# ZB3.net
KiCad netlist of a schematic drawn in Altium Designer
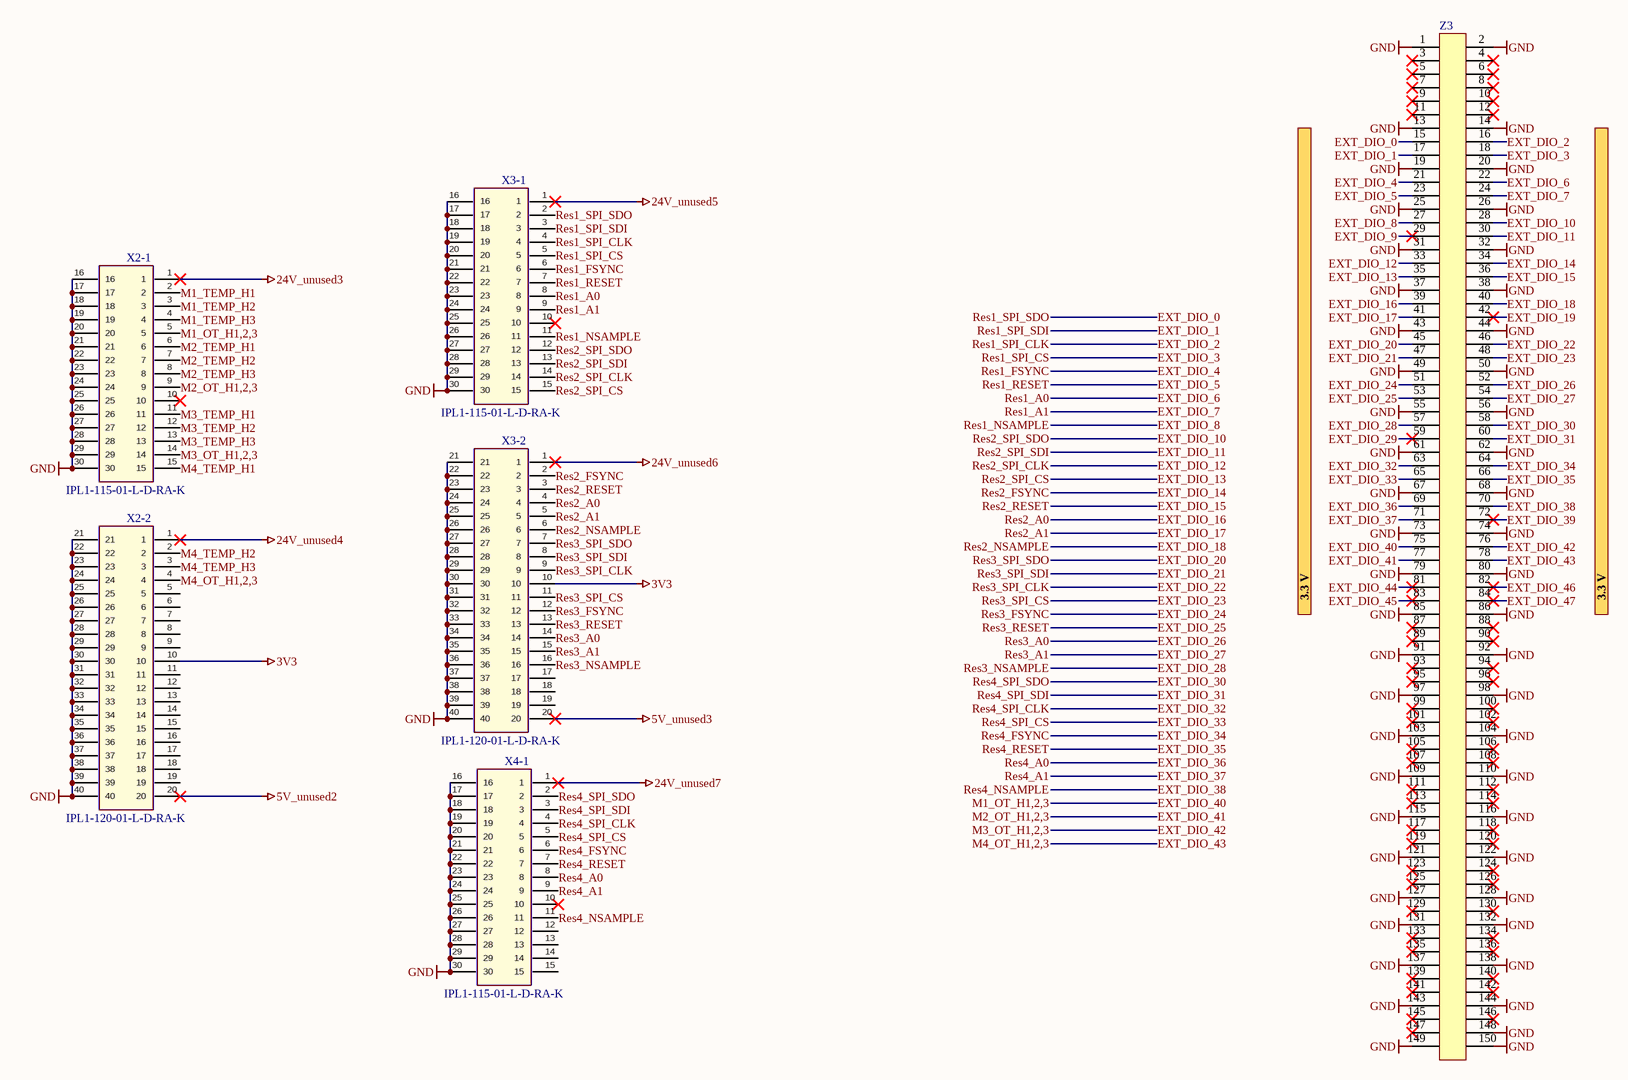
[diagram p0: ZB3.SchDoc]

(export (version "E")
  (design (tool "Eeschema 10.0.6"))
  (components
    (comp (ref "X2-1")
      (value "IPL1-115-01-L-D-RA-K")
      (footprint "IPL1-115-01-XX-D-RA")
      (description "Terminal Assembly, Double Row, Right Angle, Thru-Hole, 2.54 mm x 2.54 mm Pitch, 30 Pins")
      (fields (field (name "MANUFACTURER") "SAMTEC") (field (name "CREATED FROM") "TWendt"))
      (libsource (lib "user") (part "IPL1-115-01-XX-D-RA"))
    )
    (comp (ref "X2-2")
      (value "IPL1-120-01-L-D-RA-K")
      (footprint "IPL1-120-01-XX-D-RA")
      (description "Terminal Assembly, Double Row, Right Angle, Thru-Hole, 2.54 mm x 2.54 mm Pitch, 40 Pins")
      (fields (field (name "MANUFACTURER") "SAMTEC") (field (name "CREATED FROM") "TWendt"))
      (libsource (lib "user") (part "IPL1-120-01-XX-D-RA"))
    )
    (comp (ref "X3-1")
      (value "IPL1-115-01-L-D-RA-K")
      (footprint "IPL1-115-01-XX-D-RA")
      (description "Terminal Assembly, Double Row, Right Angle, Thru-Hole, 2.54 mm x 2.54 mm Pitch, 30 Pins")
      (fields (field (name "MANUFACTURER") "SAMTEC") (field (name "CREATED FROM") "TWendt"))
      (libsource (lib "user") (part "IPL1-115-01-XX-D-RA"))
    )
    (comp (ref "X3-2")
      (value "IPL1-120-01-L-D-RA-K")
      (footprint "IPL1-120-01-XX-D-RA")
      (description "Terminal Assembly, Double Row, Right Angle, Thru-Hole, 2.54 mm x 2.54 mm Pitch, 40 Pins")
      (fields (field (name "MANUFACTURER") "SAMTEC") (field (name "CREATED FROM") "TWendt"))
      (libsource (lib "user") (part "IPL1-120-01-XX-D-RA"))
    )
    (comp (ref "X4-1")
      (value "IPL1-115-01-L-D-RA-K")
      (footprint "IPL1-115-01-XX-D-RA")
      (description "Terminal Assembly, Double Row, Right Angle, Thru-Hole, 2.54 mm x 2.54 mm Pitch, 30 Pins")
      (fields (field (name "MANUFACTURER") "SAMTEC") (field (name "CREATED FROM") "TWendt"))
      (libsource (lib "user") (part "IPL1-115-01-XX-D-RA"))
    )
    (comp (ref "Z3")
      (value "~")
      (footprint "ERM8-075-02.0-L-DV")
      (description "0.80 mm Edge Rate Rugged High Speed")
      (fields
        (field (name "MANUFACTURER PART NUMBER") "ERM8-075-02.0-L-DV-TR")
        (field (name "MANUFACTURER") "SAMTEC")
        (field (name "CREATED FROM") "AGeiger")
      )
      (libsource (lib "user") (part "CON-150"))
    )
  )
  (nets
    (net (code "1") (name "/EXT_DIO_0") (class "Default")
      (node (ref "X3-1") (pin "2") (pinfunction "2_2") (pintype "passive"))
      (node (ref "Z3") (pin "15") (pinfunction "15_15") (pintype "passive"))
    )
    (net (code "2") (name "/EXT_DIO_1") (class "Default")
      (node (ref "X3-1") (pin "3") (pinfunction "3_3") (pintype "passive"))
      (node (ref "Z3") (pin "17") (pinfunction "17_17") (pintype "passive"))
    )
    (net (code "3") (name "/EXT_DIO_2") (class "Default")
      (node (ref "X3-1") (pin "4") (pinfunction "4_4") (pintype "passive"))
      (node (ref "Z3") (pin "16") (pinfunction "16_16") (pintype "passive"))
    )
    (net (code "4") (name "/EXT_DIO_3") (class "Default")
      (node (ref "X3-1") (pin "5") (pinfunction "5_5") (pintype "passive"))
      (node (ref "Z3") (pin "18") (pinfunction "18_18") (pintype "passive"))
    )
    (net (code "5") (name "/EXT_DIO_4") (class "Default")
      (node (ref "X3-1") (pin "6") (pinfunction "6_6") (pintype "passive"))
      (node (ref "Z3") (pin "21") (pinfunction "21_21") (pintype "passive"))
    )
    (net (code "6") (name "/EXT_DIO_5") (class "Default")
      (node (ref "X3-1") (pin "7") (pinfunction "7_7") (pintype "passive"))
      (node (ref "Z3") (pin "23") (pinfunction "23_23") (pintype "passive"))
    )
    (net (code "7") (name "/EXT_DIO_6") (class "Default")
      (node (ref "X3-1") (pin "8") (pinfunction "8_8") (pintype "passive"))
      (node (ref "Z3") (pin "22") (pinfunction "22_22") (pintype "passive"))
    )
    (net (code "8") (name "/EXT_DIO_7") (class "Default")
      (node (ref "X3-1") (pin "9") (pinfunction "9_9") (pintype "passive"))
      (node (ref "Z3") (pin "24") (pinfunction "24_24") (pintype "passive"))
    )
    (net (code "9") (name "/EXT_DIO_8") (class "Default")
      (node (ref "X3-1") (pin "11") (pinfunction "11_11") (pintype "passive"))
      (node (ref "Z3") (pin "27") (pinfunction "27_27") (pintype "passive"))
    )
    (net (code "10") (name "/EXT_DIO_9") (class "Default")
      (node (ref "Z3") (pin "29") (pinfunction "29_29") (pintype "passive+no_connect"))
    )
    (net (code "11") (name "/EXT_DIO_10") (class "Default")
      (node (ref "X3-1") (pin "12") (pinfunction "12_12") (pintype "passive"))
      (node (ref "Z3") (pin "28") (pinfunction "28_28") (pintype "passive"))
    )
    (net (code "12") (name "/EXT_DIO_11") (class "Default")
      (node (ref "X3-1") (pin "13") (pinfunction "13_13") (pintype "passive"))
      (node (ref "Z3") (pin "30") (pinfunction "30_30") (pintype "passive"))
    )
    (net (code "13") (name "/EXT_DIO_12") (class "Default")
      (node (ref "X3-1") (pin "14") (pinfunction "14_14") (pintype "passive"))
      (node (ref "Z3") (pin "33") (pinfunction "33_33") (pintype "passive"))
    )
    (net (code "14") (name "/EXT_DIO_13") (class "Default")
      (node (ref "X3-1") (pin "15") (pinfunction "15_15") (pintype "passive"))
      (node (ref "Z3") (pin "35") (pinfunction "35_35") (pintype "passive"))
    )
    (net (code "15") (name "/EXT_DIO_14") (class "Default")
      (node (ref "X3-2") (pin "2") (pinfunction "2_2") (pintype "passive"))
      (node (ref "Z3") (pin "34") (pinfunction "34_34") (pintype "passive"))
    )
    (net (code "16") (name "/EXT_DIO_15") (class "Default")
      (node (ref "X3-2") (pin "3") (pinfunction "3_3") (pintype "passive"))
      (node (ref "Z3") (pin "36") (pinfunction "36_36") (pintype "passive"))
    )
    (net (code "17") (name "/EXT_DIO_16") (class "Default")
      (node (ref "X3-2") (pin "4") (pinfunction "4_4") (pintype "passive"))
      (node (ref "Z3") (pin "39") (pinfunction "39_39") (pintype "passive"))
    )
    (net (code "18") (name "/EXT_DIO_17") (class "Default")
      (node (ref "X3-2") (pin "5") (pinfunction "5_5") (pintype "passive"))
      (node (ref "Z3") (pin "41") (pinfunction "41_41") (pintype "passive"))
    )
    (net (code "19") (name "/EXT_DIO_18") (class "Default")
      (node (ref "X3-2") (pin "6") (pinfunction "6_6") (pintype "passive"))
      (node (ref "Z3") (pin "40") (pinfunction "40_40") (pintype "passive"))
    )
    (net (code "20") (name "/EXT_DIO_19") (class "Default")
      (node (ref "Z3") (pin "42") (pinfunction "42_42") (pintype "passive+no_connect"))
    )
    (net (code "21") (name "/EXT_DIO_20") (class "Default")
      (node (ref "X3-2") (pin "7") (pinfunction "7_7") (pintype "passive"))
      (node (ref "Z3") (pin "45") (pinfunction "45_45") (pintype "passive"))
    )
    (net (code "22") (name "/EXT_DIO_21") (class "Default")
      (node (ref "X3-2") (pin "8") (pinfunction "8_8") (pintype "passive"))
      (node (ref "Z3") (pin "47") (pinfunction "47_47") (pintype "passive"))
    )
    (net (code "23") (name "/EXT_DIO_22") (class "Default")
      (node (ref "X3-2") (pin "9") (pinfunction "9_9") (pintype "passive"))
      (node (ref "Z3") (pin "46") (pinfunction "46_46") (pintype "passive"))
    )
    (net (code "24") (name "/EXT_DIO_23") (class "Default")
      (node (ref "X3-2") (pin "11") (pinfunction "11_11") (pintype "passive"))
      (node (ref "Z3") (pin "48") (pinfunction "48_48") (pintype "passive"))
    )
    (net (code "25") (name "/EXT_DIO_24") (class "Default")
      (node (ref "X3-2") (pin "12") (pinfunction "12_12") (pintype "passive"))
      (node (ref "Z3") (pin "51") (pinfunction "51_51") (pintype "passive"))
    )
    (net (code "26") (name "/EXT_DIO_25") (class "Default")
      (node (ref "X3-2") (pin "13") (pinfunction "13_13") (pintype "passive"))
      (node (ref "Z3") (pin "53") (pinfunction "53_53") (pintype "passive"))
    )
    (net (code "27") (name "/EXT_DIO_26") (class "Default")
      (node (ref "X3-2") (pin "14") (pinfunction "14_14") (pintype "passive"))
      (node (ref "Z3") (pin "52") (pinfunction "52_52") (pintype "passive"))
    )
    (net (code "28") (name "/EXT_DIO_27") (class "Default")
      (node (ref "X3-2") (pin "15") (pinfunction "15_15") (pintype "passive"))
      (node (ref "Z3") (pin "54") (pinfunction "54_54") (pintype "passive"))
    )
    (net (code "29") (name "/EXT_DIO_28") (class "Default")
      (node (ref "X3-2") (pin "16") (pinfunction "16_16") (pintype "passive"))
      (node (ref "Z3") (pin "57") (pinfunction "57_57") (pintype "passive"))
    )
    (net (code "30") (name "/EXT_DIO_29") (class "Default")
      (node (ref "Z3") (pin "59") (pinfunction "59_59") (pintype "passive+no_connect"))
    )
    (net (code "31") (name "/EXT_DIO_30") (class "Default")
      (node (ref "X4-1") (pin "2") (pinfunction "2_2") (pintype "passive"))
      (node (ref "Z3") (pin "58") (pinfunction "58_58") (pintype "passive"))
    )
    (net (code "32") (name "/EXT_DIO_31") (class "Default")
      (node (ref "X4-1") (pin "3") (pinfunction "3_3") (pintype "passive"))
      (node (ref "Z3") (pin "60") (pinfunction "60_60") (pintype "passive"))
    )
    (net (code "33") (name "/EXT_DIO_32") (class "Default")
      (node (ref "X4-1") (pin "4") (pinfunction "4_4") (pintype "passive"))
      (node (ref "Z3") (pin "63") (pinfunction "63_63") (pintype "passive"))
    )
    (net (code "34") (name "/EXT_DIO_33") (class "Default")
      (node (ref "X4-1") (pin "5") (pinfunction "5_5") (pintype "passive"))
      (node (ref "Z3") (pin "65") (pinfunction "65_65") (pintype "passive"))
    )
    (net (code "35") (name "/EXT_DIO_34") (class "Default")
      (node (ref "X4-1") (pin "6") (pinfunction "6_6") (pintype "passive"))
      (node (ref "Z3") (pin "64") (pinfunction "64_64") (pintype "passive"))
    )
    (net (code "36") (name "/EXT_DIO_35") (class "Default")
      (node (ref "X4-1") (pin "7") (pinfunction "7_7") (pintype "passive"))
      (node (ref "Z3") (pin "66") (pinfunction "66_66") (pintype "passive"))
    )
    (net (code "37") (name "/EXT_DIO_36") (class "Default")
      (node (ref "X4-1") (pin "8") (pinfunction "8_8") (pintype "passive"))
      (node (ref "Z3") (pin "69") (pinfunction "69_69") (pintype "passive"))
    )
    (net (code "38") (name "/EXT_DIO_37") (class "Default")
      (node (ref "X4-1") (pin "9") (pinfunction "9_9") (pintype "passive"))
      (node (ref "Z3") (pin "71") (pinfunction "71_71") (pintype "passive"))
    )
    (net (code "39") (name "/EXT_DIO_38") (class "Default")
      (node (ref "X4-1") (pin "11") (pinfunction "11_11") (pintype "passive"))
      (node (ref "Z3") (pin "70") (pinfunction "70_70") (pintype "passive"))
    )
    (net (code "40") (name "/EXT_DIO_39") (class "Default")
      (node (ref "Z3") (pin "72") (pinfunction "72_72") (pintype "passive+no_connect"))
    )
    (net (code "41") (name "/EXT_DIO_40") (class "Default")
      (node (ref "X2-1") (pin "5") (pinfunction "5_5") (pintype "passive"))
      (node (ref "Z3") (pin "75") (pinfunction "75_75") (pintype "passive"))
    )
    (net (code "42") (name "/EXT_DIO_41") (class "Default")
      (node (ref "X2-1") (pin "9") (pinfunction "9_9") (pintype "passive"))
      (node (ref "Z3") (pin "77") (pinfunction "77_77") (pintype "passive"))
    )
    (net (code "43") (name "/EXT_DIO_42") (class "Default")
      (node (ref "X2-1") (pin "14") (pinfunction "14_14") (pintype "passive"))
      (node (ref "Z3") (pin "76") (pinfunction "76_76") (pintype "passive"))
    )
    (net (code "44") (name "/EXT_DIO_43") (class "Default")
      (node (ref "X2-2") (pin "4") (pinfunction "4_4") (pintype "passive"))
      (node (ref "Z3") (pin "78") (pinfunction "78_78") (pintype "passive"))
    )
    (net (code "45") (name "/EXT_DIO_44") (class "Default")
      (node (ref "Z3") (pin "81") (pinfunction "81_81") (pintype "passive+no_connect"))
    )
    (net (code "46") (name "/EXT_DIO_45") (class "Default")
      (node (ref "Z3") (pin "83") (pinfunction "83_83") (pintype "passive+no_connect"))
    )
    (net (code "47") (name "/EXT_DIO_46") (class "Default")
      (node (ref "Z3") (pin "82") (pinfunction "82_82") (pintype "passive+no_connect"))
    )
    (net (code "48") (name "/EXT_DIO_47") (class "Default")
      (node (ref "Z3") (pin "84") (pinfunction "84_84") (pintype "passive+no_connect"))
    )
    (net (code "49") (name "/M1_TEMP_H1") (class "Default")
      (node (ref "X2-1") (pin "2") (pinfunction "2_2") (pintype "passive"))
    )
    (net (code "50") (name "/M1_TEMP_H2") (class "Default")
      (node (ref "X2-1") (pin "3") (pinfunction "3_3") (pintype "passive"))
    )
    (net (code "51") (name "/M1_TEMP_H3") (class "Default")
      (node (ref "X2-1") (pin "4") (pinfunction "4_4") (pintype "passive"))
    )
    (net (code "52") (name "/M2_TEMP_H1") (class "Default")
      (node (ref "X2-1") (pin "6") (pinfunction "6_6") (pintype "passive"))
    )
    (net (code "53") (name "/M2_TEMP_H2") (class "Default")
      (node (ref "X2-1") (pin "7") (pinfunction "7_7") (pintype "passive"))
    )
    (net (code "54") (name "/M2_TEMP_H3") (class "Default")
      (node (ref "X2-1") (pin "8") (pinfunction "8_8") (pintype "passive"))
    )
    (net (code "55") (name "/M3_TEMP_H1") (class "Default")
      (node (ref "X2-1") (pin "11") (pinfunction "11_11") (pintype "passive"))
    )
    (net (code "56") (name "/M3_TEMP_H2") (class "Default")
      (node (ref "X2-1") (pin "12") (pinfunction "12_12") (pintype "passive"))
    )
    (net (code "57") (name "/M3_TEMP_H3") (class "Default")
      (node (ref "X2-1") (pin "13") (pinfunction "13_13") (pintype "passive"))
    )
    (net (code "58") (name "/M4_TEMP_H1") (class "Default")
      (node (ref "X2-1") (pin "15") (pinfunction "15_15") (pintype "passive"))
    )
    (net (code "59") (name "/M4_TEMP_H2") (class "Default")
      (node (ref "X2-2") (pin "2") (pinfunction "2_2") (pintype "passive"))
    )
    (net (code "60") (name "/M4_TEMP_H3") (class "Default")
      (node (ref "X2-2") (pin "3") (pinfunction "3_3") (pintype "passive"))
    )
    (net (code "61") (name "3V3") (class "Default")
      (node (ref "X2-2") (pin "10") (pinfunction "10_10") (pintype "passive"))
      (node (ref "X3-2") (pin "10") (pinfunction "10_10") (pintype "passive"))
    )
    (net (code "62") (name "5V_unused2") (class "Default")
      (node (ref "X2-2") (pin "20") (pinfunction "20_20") (pintype "passive"))
    )
    (net (code "63") (name "5V_unused3") (class "Default")
      (node (ref "X3-2") (pin "20") (pinfunction "20_20") (pintype "passive"))
    )
    (net (code "64") (name "24V_unused3") (class "Default")
      (node (ref "X2-1") (pin "1") (pinfunction "1_1") (pintype "passive"))
    )
    (net (code "65") (name "24V_unused4") (class "Default")
      (node (ref "X2-2") (pin "1") (pinfunction "1_1") (pintype "passive"))
    )
    (net (code "66") (name "24V_unused5") (class "Default")
      (node (ref "X3-1") (pin "1") (pinfunction "1_1") (pintype "passive"))
    )
    (net (code "67") (name "24V_unused6") (class "Default")
      (node (ref "X3-2") (pin "1") (pinfunction "1_1") (pintype "passive"))
    )
    (net (code "68") (name "24V_unused7") (class "Default")
      (node (ref "X4-1") (pin "1") (pinfunction "1_1") (pintype "passive"))
    )
    (net (code "69") (name "GND") (class "Default")
      (node (ref "X2-1") (pin "16") (pinfunction "16_16") (pintype "passive"))
      (node (ref "X2-1") (pin "17") (pinfunction "17_17") (pintype "passive"))
      (node (ref "X2-1") (pin "18") (pinfunction "18_18") (pintype "passive"))
      (node (ref "X2-1") (pin "19") (pinfunction "19_19") (pintype "passive"))
      (node (ref "X2-1") (pin "20") (pinfunction "20_20") (pintype "passive"))
      (node (ref "X2-1") (pin "21") (pinfunction "21_21") (pintype "passive"))
      (node (ref "X2-1") (pin "22") (pinfunction "22_22") (pintype "passive"))
      (node (ref "X2-1") (pin "23") (pinfunction "23_23") (pintype "passive"))
      (node (ref "X2-1") (pin "24") (pinfunction "24_24") (pintype "passive"))
      (node (ref "X2-1") (pin "25") (pinfunction "25_25") (pintype "passive"))
      (node (ref "X2-1") (pin "26") (pinfunction "26_26") (pintype "passive"))
      (node (ref "X2-1") (pin "27") (pinfunction "27_27") (pintype "passive"))
      (node (ref "X2-1") (pin "28") (pinfunction "28_28") (pintype "passive"))
      (node (ref "X2-1") (pin "29") (pinfunction "29_29") (pintype "passive"))
      (node (ref "X2-1") (pin "30") (pinfunction "30_30") (pintype "passive"))
      (node (ref "X2-2") (pin "21") (pinfunction "21_21") (pintype "passive"))
      (node (ref "X2-2") (pin "22") (pinfunction "22_22") (pintype "passive"))
      (node (ref "X2-2") (pin "23") (pinfunction "23_23") (pintype "passive"))
      (node (ref "X2-2") (pin "24") (pinfunction "24_24") (pintype "passive"))
      (node (ref "X2-2") (pin "25") (pinfunction "25_25") (pintype "passive"))
      (node (ref "X2-2") (pin "26") (pinfunction "26_26") (pintype "passive"))
      (node (ref "X2-2") (pin "27") (pinfunction "27_27") (pintype "passive"))
      (node (ref "X2-2") (pin "28") (pinfunction "28_28") (pintype "passive"))
      (node (ref "X2-2") (pin "29") (pinfunction "29_29") (pintype "passive"))
      (node (ref "X2-2") (pin "30") (pinfunction "30_30") (pintype "passive"))
      (node (ref "X2-2") (pin "31") (pinfunction "31_31") (pintype "passive"))
      (node (ref "X2-2") (pin "32") (pinfunction "32_32") (pintype "passive"))
      (node (ref "X2-2") (pin "33") (pinfunction "33_33") (pintype "passive"))
      (node (ref "X2-2") (pin "34") (pinfunction "34_34") (pintype "passive"))
      (node (ref "X2-2") (pin "35") (pinfunction "35_35") (pintype "passive"))
      (node (ref "X2-2") (pin "36") (pinfunction "36_36") (pintype "passive"))
      (node (ref "X2-2") (pin "37") (pinfunction "37_37") (pintype "passive"))
      (node (ref "X2-2") (pin "38") (pinfunction "38_38") (pintype "passive"))
      (node (ref "X2-2") (pin "39") (pinfunction "39_39") (pintype "passive"))
      (node (ref "X2-2") (pin "40") (pinfunction "40_40") (pintype "passive"))
      (node (ref "X3-1") (pin "16") (pinfunction "16_16") (pintype "passive"))
      (node (ref "X3-1") (pin "17") (pinfunction "17_17") (pintype "passive"))
      (node (ref "X3-1") (pin "18") (pinfunction "18_18") (pintype "passive"))
      (node (ref "X3-1") (pin "19") (pinfunction "19_19") (pintype "passive"))
      (node (ref "X3-1") (pin "20") (pinfunction "20_20") (pintype "passive"))
      (node (ref "X3-1") (pin "21") (pinfunction "21_21") (pintype "passive"))
      (node (ref "X3-1") (pin "22") (pinfunction "22_22") (pintype "passive"))
      (node (ref "X3-1") (pin "23") (pinfunction "23_23") (pintype "passive"))
      (node (ref "X3-1") (pin "24") (pinfunction "24_24") (pintype "passive"))
      (node (ref "X3-1") (pin "25") (pinfunction "25_25") (pintype "passive"))
      (node (ref "X3-1") (pin "26") (pinfunction "26_26") (pintype "passive"))
      (node (ref "X3-1") (pin "27") (pinfunction "27_27") (pintype "passive"))
      (node (ref "X3-1") (pin "28") (pinfunction "28_28") (pintype "passive"))
      (node (ref "X3-1") (pin "29") (pinfunction "29_29") (pintype "passive"))
      (node (ref "X3-1") (pin "30") (pinfunction "30_30") (pintype "passive"))
      (node (ref "X3-2") (pin "21") (pinfunction "21_21") (pintype "passive"))
      (node (ref "X3-2") (pin "22") (pinfunction "22_22") (pintype "passive"))
      (node (ref "X3-2") (pin "23") (pinfunction "23_23") (pintype "passive"))
      (node (ref "X3-2") (pin "24") (pinfunction "24_24") (pintype "passive"))
      (node (ref "X3-2") (pin "25") (pinfunction "25_25") (pintype "passive"))
      (node (ref "X3-2") (pin "26") (pinfunction "26_26") (pintype "passive"))
      (node (ref "X3-2") (pin "27") (pinfunction "27_27") (pintype "passive"))
      (node (ref "X3-2") (pin "28") (pinfunction "28_28") (pintype "passive"))
      (node (ref "X3-2") (pin "29") (pinfunction "29_29") (pintype "passive"))
      (node (ref "X3-2") (pin "30") (pinfunction "30_30") (pintype "passive"))
      (node (ref "X3-2") (pin "31") (pinfunction "31_31") (pintype "passive"))
      (node (ref "X3-2") (pin "32") (pinfunction "32_32") (pintype "passive"))
      (node (ref "X3-2") (pin "33") (pinfunction "33_33") (pintype "passive"))
      (node (ref "X3-2") (pin "34") (pinfunction "34_34") (pintype "passive"))
      (node (ref "X3-2") (pin "35") (pinfunction "35_35") (pintype "passive"))
      (node (ref "X3-2") (pin "36") (pinfunction "36_36") (pintype "passive"))
      (node (ref "X3-2") (pin "37") (pinfunction "37_37") (pintype "passive"))
      (node (ref "X3-2") (pin "38") (pinfunction "38_38") (pintype "passive"))
      (node (ref "X3-2") (pin "39") (pinfunction "39_39") (pintype "passive"))
      (node (ref "X3-2") (pin "40") (pinfunction "40_40") (pintype "passive"))
      (node (ref "X4-1") (pin "16") (pinfunction "16_16") (pintype "passive"))
      (node (ref "X4-1") (pin "17") (pinfunction "17_17") (pintype "passive"))
      (node (ref "X4-1") (pin "18") (pinfunction "18_18") (pintype "passive"))
      (node (ref "X4-1") (pin "19") (pinfunction "19_19") (pintype "passive"))
      (node (ref "X4-1") (pin "20") (pinfunction "20_20") (pintype "passive"))
      (node (ref "X4-1") (pin "21") (pinfunction "21_21") (pintype "passive"))
      (node (ref "X4-1") (pin "22") (pinfunction "22_22") (pintype "passive"))
      (node (ref "X4-1") (pin "23") (pinfunction "23_23") (pintype "passive"))
      (node (ref "X4-1") (pin "24") (pinfunction "24_24") (pintype "passive"))
      (node (ref "X4-1") (pin "25") (pinfunction "25_25") (pintype "passive"))
      (node (ref "X4-1") (pin "26") (pinfunction "26_26") (pintype "passive"))
      (node (ref "X4-1") (pin "27") (pinfunction "27_27") (pintype "passive"))
      (node (ref "X4-1") (pin "28") (pinfunction "28_28") (pintype "passive"))
      (node (ref "X4-1") (pin "29") (pinfunction "29_29") (pintype "passive"))
      (node (ref "X4-1") (pin "30") (pinfunction "30_30") (pintype "passive"))
      (node (ref "Z3") (pin "1") (pinfunction "1_1") (pintype "passive"))
      (node (ref "Z3") (pin "103") (pinfunction "103_103") (pintype "passive"))
      (node (ref "Z3") (pin "104") (pinfunction "104_104") (pintype "passive"))
      (node (ref "Z3") (pin "109") (pinfunction "109_109") (pintype "passive"))
      (node (ref "Z3") (pin "110") (pinfunction "110_110") (pintype "passive"))
      (node (ref "Z3") (pin "115") (pinfunction "115_115") (pintype "passive"))
      (node (ref "Z3") (pin "116") (pinfunction "116_116") (pintype "passive"))
      (node (ref "Z3") (pin "121") (pinfunction "121_121") (pintype "passive"))
      (node (ref "Z3") (pin "122") (pinfunction "122_122") (pintype "passive"))
      (node (ref "Z3") (pin "127") (pinfunction "127_127") (pintype "passive"))
      (node (ref "Z3") (pin "128") (pinfunction "128_128") (pintype "passive"))
      (node (ref "Z3") (pin "13") (pinfunction "13_13") (pintype "passive"))
      (node (ref "Z3") (pin "131") (pinfunction "131_131") (pintype "passive"))
      (node (ref "Z3") (pin "132") (pinfunction "132_132") (pintype "passive"))
      (node (ref "Z3") (pin "137") (pinfunction "137_137") (pintype "passive"))
      (node (ref "Z3") (pin "138") (pinfunction "138_138") (pintype "passive"))
      (node (ref "Z3") (pin "14") (pinfunction "14_14") (pintype "passive"))
      (node (ref "Z3") (pin "143") (pinfunction "143_143") (pintype "passive"))
      (node (ref "Z3") (pin "144") (pinfunction "144_144") (pintype "passive"))
      (node (ref "Z3") (pin "148") (pinfunction "148_148") (pintype "passive"))
      (node (ref "Z3") (pin "149") (pinfunction "149_149") (pintype "passive"))
      (node (ref "Z3") (pin "150") (pinfunction "150_150") (pintype "passive"))
      (node (ref "Z3") (pin "19") (pinfunction "19_19") (pintype "passive"))
      (node (ref "Z3") (pin "2") (pinfunction "2_2") (pintype "passive"))
      (node (ref "Z3") (pin "20") (pinfunction "20_20") (pintype "passive"))
      (node (ref "Z3") (pin "25") (pinfunction "25_25") (pintype "passive"))
      (node (ref "Z3") (pin "26") (pinfunction "26_26") (pintype "passive"))
      (node (ref "Z3") (pin "31") (pinfunction "31_31") (pintype "passive"))
      (node (ref "Z3") (pin "32") (pinfunction "32_32") (pintype "passive"))
      (node (ref "Z3") (pin "37") (pinfunction "37_37") (pintype "passive"))
      (node (ref "Z3") (pin "38") (pinfunction "38_38") (pintype "passive"))
      (node (ref "Z3") (pin "43") (pinfunction "43_43") (pintype "passive"))
      (node (ref "Z3") (pin "44") (pinfunction "44_44") (pintype "passive"))
      (node (ref "Z3") (pin "49") (pinfunction "49_49") (pintype "passive"))
      (node (ref "Z3") (pin "50") (pinfunction "50_50") (pintype "passive"))
      (node (ref "Z3") (pin "55") (pinfunction "55_55") (pintype "passive"))
      (node (ref "Z3") (pin "56") (pinfunction "56_56") (pintype "passive"))
      (node (ref "Z3") (pin "61") (pinfunction "61_61") (pintype "passive"))
      (node (ref "Z3") (pin "62") (pinfunction "62_62") (pintype "passive"))
      (node (ref "Z3") (pin "67") (pinfunction "67_67") (pintype "passive"))
      (node (ref "Z3") (pin "68") (pinfunction "68_68") (pintype "passive"))
      (node (ref "Z3") (pin "73") (pinfunction "73_73") (pintype "passive"))
      (node (ref "Z3") (pin "74") (pinfunction "74_74") (pintype "passive"))
      (node (ref "Z3") (pin "79") (pinfunction "79_79") (pintype "passive"))
      (node (ref "Z3") (pin "80") (pinfunction "80_80") (pintype "passive"))
      (node (ref "Z3") (pin "85") (pinfunction "85_85") (pintype "passive"))
      (node (ref "Z3") (pin "86") (pinfunction "86_86") (pintype "passive"))
      (node (ref "Z3") (pin "91") (pinfunction "91_91") (pintype "passive"))
      (node (ref "Z3") (pin "92") (pinfunction "92_92") (pintype "passive"))
      (node (ref "Z3") (pin "97") (pinfunction "97_97") (pintype "passive"))
      (node (ref "Z3") (pin "98") (pinfunction "98_98") (pintype "passive"))
    )
    (net (code "70") (name "unconnected-(X2-1-Pad10)") (class "Default")
      (node (ref "X2-1") (pin "10") (pinfunction "10_10") (pintype "passive+no_connect"))
    )
    (net (code "71") (name "unconnected-(X2-2-Pad5)") (class "Default")
      (node (ref "X2-2") (pin "5") (pinfunction "5_5") (pintype "passive"))
    )
    (net (code "72") (name "unconnected-(X2-2-Pad6)") (class "Default")
      (node (ref "X2-2") (pin "6") (pinfunction "6_6") (pintype "passive"))
    )
    (net (code "73") (name "unconnected-(X2-2-Pad7)") (class "Default")
      (node (ref "X2-2") (pin "7") (pinfunction "7_7") (pintype "passive"))
    )
    (net (code "74") (name "unconnected-(X2-2-Pad8)") (class "Default")
      (node (ref "X2-2") (pin "8") (pinfunction "8_8") (pintype "passive"))
    )
    (net (code "75") (name "unconnected-(X2-2-Pad9)") (class "Default")
      (node (ref "X2-2") (pin "9") (pinfunction "9_9") (pintype "passive"))
    )
    (net (code "76") (name "unconnected-(X2-2-Pad11)") (class "Default")
      (node (ref "X2-2") (pin "11") (pinfunction "11_11") (pintype "passive"))
    )
    (net (code "77") (name "unconnected-(X2-2-Pad12)") (class "Default")
      (node (ref "X2-2") (pin "12") (pinfunction "12_12") (pintype "passive"))
    )
    (net (code "78") (name "unconnected-(X2-2-Pad13)") (class "Default")
      (node (ref "X2-2") (pin "13") (pinfunction "13_13") (pintype "passive"))
    )
    (net (code "79") (name "unconnected-(X2-2-Pad14)") (class "Default")
      (node (ref "X2-2") (pin "14") (pinfunction "14_14") (pintype "passive"))
    )
    (net (code "80") (name "unconnected-(X2-2-Pad15)") (class "Default")
      (node (ref "X2-2") (pin "15") (pinfunction "15_15") (pintype "passive"))
    )
    (net (code "81") (name "unconnected-(X2-2-Pad16)") (class "Default")
      (node (ref "X2-2") (pin "16") (pinfunction "16_16") (pintype "passive"))
    )
    (net (code "82") (name "unconnected-(X2-2-Pad17)") (class "Default")
      (node (ref "X2-2") (pin "17") (pinfunction "17_17") (pintype "passive"))
    )
    (net (code "83") (name "unconnected-(X2-2-Pad18)") (class "Default")
      (node (ref "X2-2") (pin "18") (pinfunction "18_18") (pintype "passive"))
    )
    (net (code "84") (name "unconnected-(X2-2-Pad19)") (class "Default")
      (node (ref "X2-2") (pin "19") (pinfunction "19_19") (pintype "passive"))
    )
    (net (code "85") (name "unconnected-(X3-1-Pad10)") (class "Default")
      (node (ref "X3-1") (pin "10") (pinfunction "10_10") (pintype "passive+no_connect"))
    )
    (net (code "86") (name "unconnected-(X3-2-Pad17)") (class "Default")
      (node (ref "X3-2") (pin "17") (pinfunction "17_17") (pintype "passive"))
    )
    (net (code "87") (name "unconnected-(X3-2-Pad18)") (class "Default")
      (node (ref "X3-2") (pin "18") (pinfunction "18_18") (pintype "passive"))
    )
    (net (code "88") (name "unconnected-(X3-2-Pad19)") (class "Default")
      (node (ref "X3-2") (pin "19") (pinfunction "19_19") (pintype "passive"))
    )
    (net (code "89") (name "unconnected-(X4-1-Pad10)") (class "Default")
      (node (ref "X4-1") (pin "10") (pinfunction "10_10") (pintype "passive+no_connect"))
    )
    (net (code "90") (name "unconnected-(X4-1-Pad12)") (class "Default")
      (node (ref "X4-1") (pin "12") (pinfunction "12_12") (pintype "passive"))
    )
    (net (code "91") (name "unconnected-(X4-1-Pad13)") (class "Default")
      (node (ref "X4-1") (pin "13") (pinfunction "13_13") (pintype "passive"))
    )
    (net (code "92") (name "unconnected-(X4-1-Pad14)") (class "Default")
      (node (ref "X4-1") (pin "14") (pinfunction "14_14") (pintype "passive"))
    )
    (net (code "93") (name "unconnected-(X4-1-Pad15)") (class "Default")
      (node (ref "X4-1") (pin "15") (pinfunction "15_15") (pintype "passive"))
    )
    (net (code "94") (name "unconnected-(Z3-Pad3)") (class "Default")
      (node (ref "Z3") (pin "3") (pinfunction "3_3") (pintype "passive+no_connect"))
    )
    (net (code "95") (name "unconnected-(Z3-Pad4)") (class "Default")
      (node (ref "Z3") (pin "4") (pinfunction "4_4") (pintype "passive+no_connect"))
    )
    (net (code "96") (name "unconnected-(Z3-Pad5)") (class "Default")
      (node (ref "Z3") (pin "5") (pinfunction "5_5") (pintype "passive+no_connect"))
    )
    (net (code "97") (name "unconnected-(Z3-Pad6)") (class "Default")
      (node (ref "Z3") (pin "6") (pinfunction "6_6") (pintype "passive+no_connect"))
    )
    (net (code "98") (name "unconnected-(Z3-Pad7)") (class "Default")
      (node (ref "Z3") (pin "7") (pinfunction "7_7") (pintype "passive+no_connect"))
    )
    (net (code "99") (name "unconnected-(Z3-Pad8)") (class "Default")
      (node (ref "Z3") (pin "8") (pinfunction "8_8") (pintype "passive+no_connect"))
    )
    (net (code "100") (name "unconnected-(Z3-Pad9)") (class "Default")
      (node (ref "Z3") (pin "9") (pinfunction "9_9") (pintype "passive+no_connect"))
    )
    (net (code "101") (name "unconnected-(Z3-Pad10)") (class "Default")
      (node (ref "Z3") (pin "10") (pinfunction "10_10") (pintype "passive+no_connect"))
    )
    (net (code "102") (name "unconnected-(Z3-Pad11)") (class "Default")
      (node (ref "Z3") (pin "11") (pinfunction "11_11") (pintype "passive+no_connect"))
    )
    (net (code "103") (name "unconnected-(Z3-Pad12)") (class "Default")
      (node (ref "Z3") (pin "12") (pinfunction "12_12") (pintype "passive+no_connect"))
    )
    (net (code "104") (name "unconnected-(Z3-Pad87)") (class "Default")
      (node (ref "Z3") (pin "87") (pinfunction "87_87") (pintype "passive+no_connect"))
    )
    (net (code "105") (name "unconnected-(Z3-Pad88)") (class "Default")
      (node (ref "Z3") (pin "88") (pinfunction "88_88") (pintype "passive+no_connect"))
    )
    (net (code "106") (name "unconnected-(Z3-Pad89)") (class "Default")
      (node (ref "Z3") (pin "89") (pinfunction "89_89") (pintype "passive+no_connect"))
    )
    (net (code "107") (name "unconnected-(Z3-Pad90)") (class "Default")
      (node (ref "Z3") (pin "90") (pinfunction "90_90") (pintype "passive+no_connect"))
    )
    (net (code "108") (name "unconnected-(Z3-Pad93)") (class "Default")
      (node (ref "Z3") (pin "93") (pinfunction "93_93") (pintype "passive+no_connect"))
    )
    (net (code "109") (name "unconnected-(Z3-Pad94)") (class "Default")
      (node (ref "Z3") (pin "94") (pinfunction "94_94") (pintype "passive+no_connect"))
    )
    (net (code "110") (name "unconnected-(Z3-Pad95)") (class "Default")
      (node (ref "Z3") (pin "95") (pinfunction "95_95") (pintype "passive+no_connect"))
    )
    (net (code "111") (name "unconnected-(Z3-Pad96)") (class "Default")
      (node (ref "Z3") (pin "96") (pinfunction "96_96") (pintype "passive+no_connect"))
    )
    (net (code "112") (name "unconnected-(Z3-Pad99)") (class "Default")
      (node (ref "Z3") (pin "99") (pinfunction "99_99") (pintype "passive+no_connect"))
    )
    (net (code "113") (name "unconnected-(Z3-Pad100)") (class "Default")
      (node (ref "Z3") (pin "100") (pinfunction "100_100") (pintype "passive+no_connect"))
    )
    (net (code "114") (name "unconnected-(Z3-Pad101)") (class "Default")
      (node (ref "Z3") (pin "101") (pinfunction "101_101") (pintype "passive+no_connect"))
    )
    (net (code "115") (name "unconnected-(Z3-Pad102)") (class "Default")
      (node (ref "Z3") (pin "102") (pinfunction "102_102") (pintype "passive+no_connect"))
    )
    (net (code "116") (name "unconnected-(Z3-Pad105)") (class "Default")
      (node (ref "Z3") (pin "105") (pinfunction "105_105") (pintype "passive+no_connect"))
    )
    (net (code "117") (name "unconnected-(Z3-Pad106)") (class "Default")
      (node (ref "Z3") (pin "106") (pinfunction "106_106") (pintype "passive+no_connect"))
    )
    (net (code "118") (name "unconnected-(Z3-Pad107)") (class "Default")
      (node (ref "Z3") (pin "107") (pinfunction "107_107") (pintype "passive+no_connect"))
    )
    (net (code "119") (name "unconnected-(Z3-Pad108)") (class "Default")
      (node (ref "Z3") (pin "108") (pinfunction "108_108") (pintype "passive+no_connect"))
    )
    (net (code "120") (name "unconnected-(Z3-Pad111)") (class "Default")
      (node (ref "Z3") (pin "111") (pinfunction "111_111") (pintype "passive+no_connect"))
    )
    (net (code "121") (name "unconnected-(Z3-Pad112)") (class "Default")
      (node (ref "Z3") (pin "112") (pinfunction "112_112") (pintype "passive+no_connect"))
    )
    (net (code "122") (name "unconnected-(Z3-Pad113)") (class "Default")
      (node (ref "Z3") (pin "113") (pinfunction "113_113") (pintype "passive+no_connect"))
    )
    (net (code "123") (name "unconnected-(Z3-Pad114)") (class "Default")
      (node (ref "Z3") (pin "114") (pinfunction "114_114") (pintype "passive+no_connect"))
    )
    (net (code "124") (name "unconnected-(Z3-Pad117)") (class "Default")
      (node (ref "Z3") (pin "117") (pinfunction "117_117") (pintype "passive+no_connect"))
    )
    (net (code "125") (name "unconnected-(Z3-Pad118)") (class "Default")
      (node (ref "Z3") (pin "118") (pinfunction "118_118") (pintype "passive+no_connect"))
    )
    (net (code "126") (name "unconnected-(Z3-Pad119)") (class "Default")
      (node (ref "Z3") (pin "119") (pinfunction "119_119") (pintype "passive+no_connect"))
    )
    (net (code "127") (name "unconnected-(Z3-Pad120)") (class "Default")
      (node (ref "Z3") (pin "120") (pinfunction "120_120") (pintype "passive+no_connect"))
    )
    (net (code "128") (name "unconnected-(Z3-Pad123)") (class "Default")
      (node (ref "Z3") (pin "123") (pinfunction "123_123") (pintype "passive+no_connect"))
    )
    (net (code "129") (name "unconnected-(Z3-Pad124)") (class "Default")
      (node (ref "Z3") (pin "124") (pinfunction "124_124") (pintype "passive+no_connect"))
    )
    (net (code "130") (name "unconnected-(Z3-Pad125)") (class "Default")
      (node (ref "Z3") (pin "125") (pinfunction "125_125") (pintype "passive+no_connect"))
    )
    (net (code "131") (name "unconnected-(Z3-Pad126)") (class "Default")
      (node (ref "Z3") (pin "126") (pinfunction "126_126") (pintype "passive+no_connect"))
    )
    (net (code "132") (name "unconnected-(Z3-Pad129)") (class "Default")
      (node (ref "Z3") (pin "129") (pinfunction "129_129") (pintype "passive+no_connect"))
    )
    (net (code "133") (name "unconnected-(Z3-Pad130)") (class "Default")
      (node (ref "Z3") (pin "130") (pinfunction "130_130") (pintype "passive+no_connect"))
    )
    (net (code "134") (name "unconnected-(Z3-Pad133)") (class "Default")
      (node (ref "Z3") (pin "133") (pinfunction "133_133") (pintype "passive+no_connect"))
    )
    (net (code "135") (name "unconnected-(Z3-Pad134)") (class "Default")
      (node (ref "Z3") (pin "134") (pinfunction "134_134") (pintype "passive+no_connect"))
    )
    (net (code "136") (name "unconnected-(Z3-Pad135)") (class "Default")
      (node (ref "Z3") (pin "135") (pinfunction "135_135") (pintype "passive+no_connect"))
    )
    (net (code "137") (name "unconnected-(Z3-Pad136)") (class "Default")
      (node (ref "Z3") (pin "136") (pinfunction "136_136") (pintype "passive+no_connect"))
    )
    (net (code "138") (name "unconnected-(Z3-Pad139)") (class "Default")
      (node (ref "Z3") (pin "139") (pinfunction "139_139") (pintype "passive+no_connect"))
    )
    (net (code "139") (name "unconnected-(Z3-Pad140)") (class "Default")
      (node (ref "Z3") (pin "140") (pinfunction "140_140") (pintype "passive+no_connect"))
    )
    (net (code "140") (name "unconnected-(Z3-Pad141)") (class "Default")
      (node (ref "Z3") (pin "141") (pinfunction "141_141") (pintype "passive+no_connect"))
    )
    (net (code "141") (name "unconnected-(Z3-Pad142)") (class "Default")
      (node (ref "Z3") (pin "142") (pinfunction "142_142") (pintype "passive+no_connect"))
    )
    (net (code "142") (name "unconnected-(Z3-Pad145)") (class "Default")
      (node (ref "Z3") (pin "145") (pinfunction "145_145") (pintype "passive+no_connect"))
    )
    (net (code "143") (name "unconnected-(Z3-Pad146)") (class "Default")
      (node (ref "Z3") (pin "146") (pinfunction "146_146") (pintype "passive+no_connect"))
    )
    (net (code "144") (name "unconnected-(Z3-Pad147)") (class "Default")
      (node (ref "Z3") (pin "147") (pinfunction "147_147") (pintype "passive+no_connect"))
    )
  )
)
